# wlpkt1_wejscia.net
KiCad netlist of a schematic drawn in Altium Designer
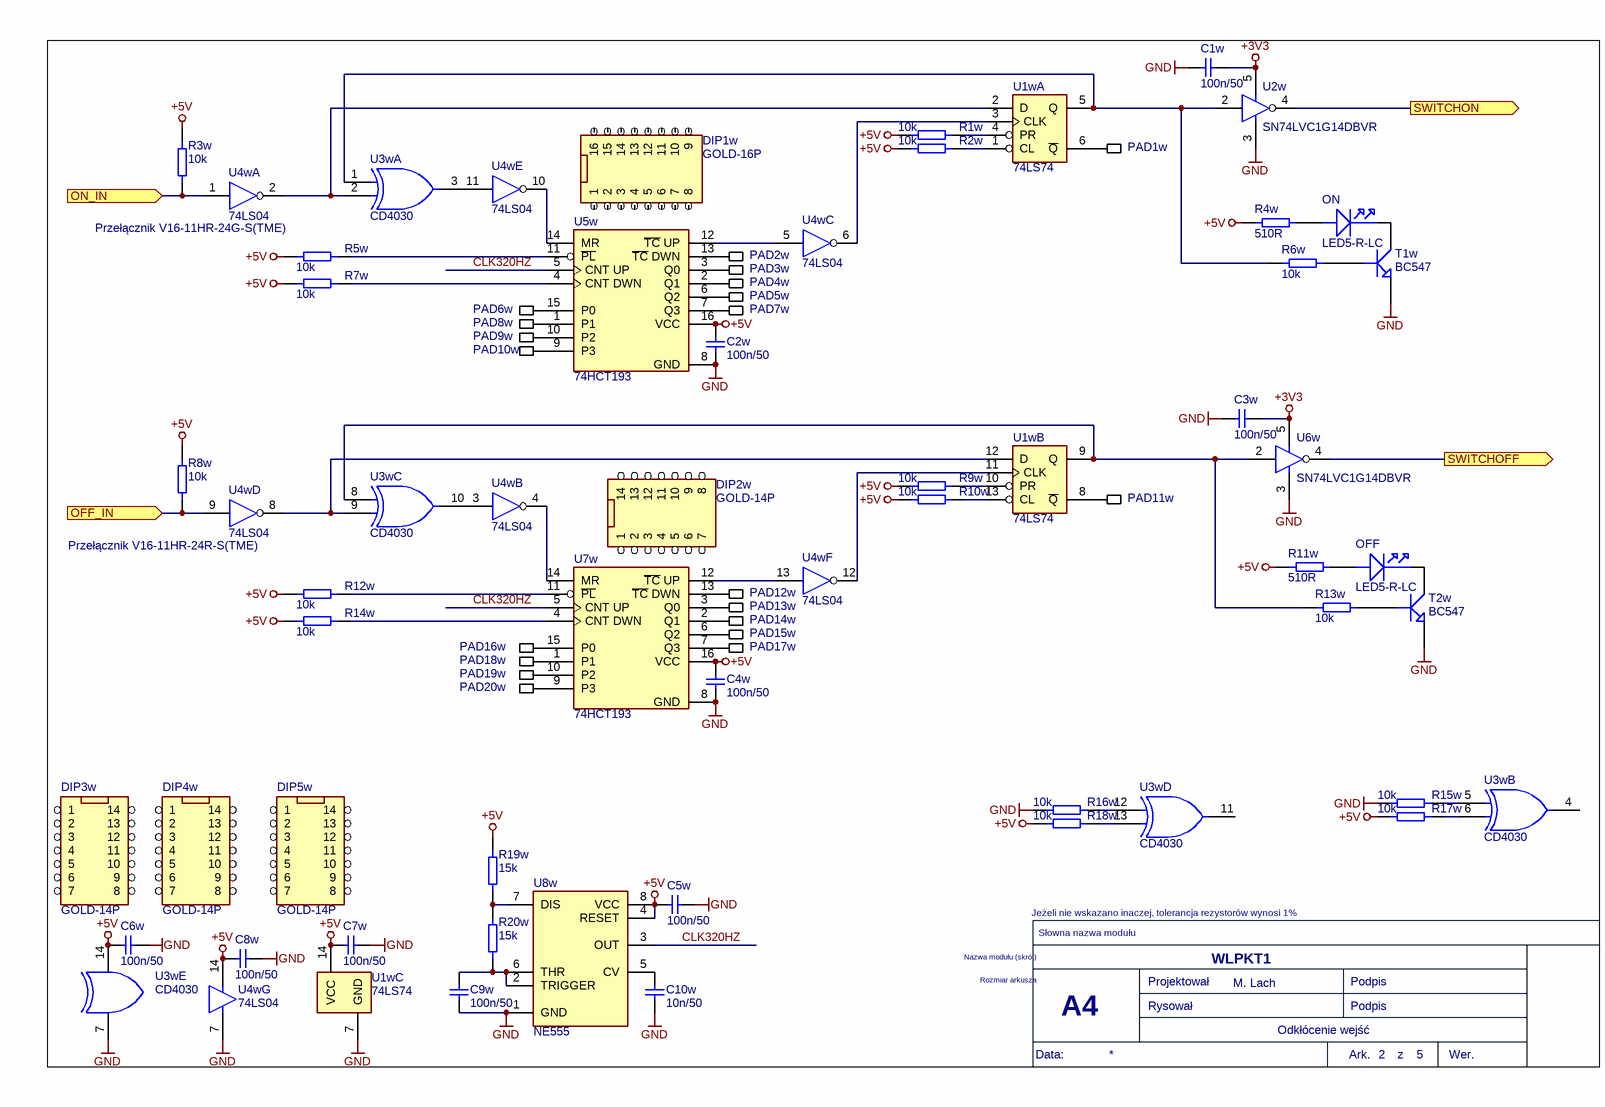
[diagram p0: wlpkt1_wejscia.SchDoc]

(export (version "E")
  (design (tool "Eeschema 10.0.6"))
  (components
    (comp (ref "C1w") (value "100n/50") (footprint "0805") (libsource (lib "PartsMySQL") (part "C")))
    (comp (ref "C2w") (value "100n/50") (footprint "0805") (libsource (lib "PartsMySQL") (part "C")))
    (comp (ref "C3w") (value "100n/50") (footprint "0805") (libsource (lib "PartsMySQL") (part "C")))
    (comp (ref "C4w") (value "100n/50") (footprint "0805") (libsource (lib "PartsMySQL") (part "C")))
    (comp (ref "C5w") (value "100n/50") (footprint "0805") (libsource (lib "PartsMySQL") (part "C")))
    (comp (ref "C6w") (value "100n/50") (footprint "0805") (libsource (lib "PartsMySQL") (part "C")))
    (comp (ref "C7w") (value "100n/50") (footprint "0805") (libsource (lib "PartsMySQL") (part "C")))
    (comp (ref "C8w") (value "100n/50") (footprint "0805") (libsource (lib "PartsMySQL") (part "C")))
    (comp (ref "C9w") (value "100n/50") (footprint "0805") (libsource (lib "PartsMySQL") (part "C")))
    (comp (ref "C10w") (value "10n/50") (footprint "0805") (libsource (lib "PartsMySQL") (part "C")))
    (comp (ref "DIP1w") (value "GOLD-16P") (libsource (lib "PartsMySQL") (part "DIP16MECH")))
    (comp (ref "DIP2w") (value "GOLD-14P") (libsource (lib "") (part "DIP14MECH_1")))
    (comp (ref "DIP3w") (value "GOLD-14P") (libsource (lib "PartsMySQL") (part "DIP14MECH")))
    (comp (ref "DIP4w") (value "GOLD-14P") (libsource (lib "PartsMySQL") (part "DIP14MECH")))
    (comp (ref "DIP5w") (value "GOLD-14P") (libsource (lib "PartsMySQL") (part "DIP14MECH")))
    (comp (ref "OFF") (value "LED5-R-LC") (footprint "CO26") (libsource (lib "PartsMySQL") (part "LED")))
    (comp (ref "ON") (value "LED5-R-LC") (footprint "CO26") (libsource (lib "PartsMySQL") (part "LED")))
    (comp (ref "PAD1w")
      (value "PAD0_6MM")
      (footprint "PAD0_6MM")
      (libsource (lib "PartsMySQL") (part "CLAMP_NOBOM"))
    )
    (comp (ref "PAD2w")
      (value "PAD0_6MM")
      (footprint "PAD0_6MM")
      (libsource (lib "PartsMySQL") (part "CLAMP_NOBOM"))
    )
    (comp (ref "PAD3w")
      (value "PAD0_6MM")
      (footprint "PAD0_6MM")
      (libsource (lib "PartsMySQL") (part "CLAMP_NOBOM"))
    )
    (comp (ref "PAD4w")
      (value "PAD0_6MM")
      (footprint "PAD0_6MM")
      (libsource (lib "PartsMySQL") (part "CLAMP_NOBOM"))
    )
    (comp (ref "PAD5w")
      (value "PAD0_6MM")
      (footprint "PAD0_6MM")
      (libsource (lib "PartsMySQL") (part "CLAMP_NOBOM"))
    )
    (comp (ref "PAD6w") (value "PAD0_6MM") (footprint "PAD0_6MM") (libsource (lib "") (part "CLAMP_NOBOM_1")))
    (comp (ref "PAD7w")
      (value "PAD0_6MM")
      (footprint "PAD0_6MM")
      (libsource (lib "PartsMySQL") (part "CLAMP_NOBOM"))
    )
    (comp (ref "PAD8w") (value "PAD0_6MM") (footprint "PAD0_6MM") (libsource (lib "") (part "CLAMP_NOBOM_1")))
    (comp (ref "PAD9w") (value "PAD0_6MM") (footprint "PAD0_6MM") (libsource (lib "") (part "CLAMP_NOBOM_1")))
    (comp (ref "PAD10w")
      (value "PAD0_6MM")
      (footprint "PAD0_6MM")
      (libsource (lib "") (part "CLAMP_NOBOM_1"))
    )
    (comp (ref "PAD11w")
      (value "PAD0_6MM")
      (footprint "PAD0_6MM")
      (libsource (lib "PartsMySQL") (part "CLAMP_NOBOM"))
    )
    (comp (ref "PAD12w")
      (value "PAD0_6MM")
      (footprint "PAD0_6MM")
      (libsource (lib "PartsMySQL") (part "CLAMP_NOBOM"))
    )
    (comp (ref "PAD13w")
      (value "PAD0_6MM")
      (footprint "PAD0_6MM")
      (libsource (lib "PartsMySQL") (part "CLAMP_NOBOM"))
    )
    (comp (ref "PAD14w")
      (value "PAD0_6MM")
      (footprint "PAD0_6MM")
      (libsource (lib "PartsMySQL") (part "CLAMP_NOBOM"))
    )
    (comp (ref "PAD15w")
      (value "PAD0_6MM")
      (footprint "PAD0_6MM")
      (libsource (lib "PartsMySQL") (part "CLAMP_NOBOM"))
    )
    (comp (ref "PAD16w")
      (value "PAD0_6MM")
      (footprint "PAD0_6MM")
      (libsource (lib "") (part "CLAMP_NOBOM_1"))
    )
    (comp (ref "PAD17w")
      (value "PAD0_6MM")
      (footprint "PAD0_6MM")
      (libsource (lib "PartsMySQL") (part "CLAMP_NOBOM"))
    )
    (comp (ref "PAD18w")
      (value "PAD0_6MM")
      (footprint "PAD0_6MM")
      (libsource (lib "") (part "CLAMP_NOBOM_1"))
    )
    (comp (ref "PAD19w")
      (value "PAD0_6MM")
      (footprint "PAD0_6MM")
      (libsource (lib "") (part "CLAMP_NOBOM_1"))
    )
    (comp (ref "PAD20w")
      (value "PAD0_6MM")
      (footprint "PAD0_6MM")
      (libsource (lib "") (part "CLAMP_NOBOM_1"))
    )
    (comp (ref "R1w") (value "10k") (footprint "0805R") (libsource (lib "PartsMySQL") (part "R")))
    (comp (ref "R2w") (value "10k") (footprint "0805R") (libsource (lib "PartsMySQL") (part "R")))
    (comp (ref "R3w") (value "10k") (footprint "0805R") (libsource (lib "PartsMySQL") (part "R")))
    (comp (ref "R4w") (value "510R") (footprint "R402510") (libsource (lib "PartsMySQL") (part "R")))
    (comp (ref "R5w") (value "10k") (footprint "0805R") (libsource (lib "PartsMySQL") (part "R")))
    (comp (ref "R6w") (value "10k") (footprint "0805R") (libsource (lib "PartsMySQL") (part "R")))
    (comp (ref "R7w") (value "10k") (footprint "0805R") (libsource (lib "PartsMySQL") (part "R")))
    (comp (ref "R8w") (value "10k") (footprint "0805R") (libsource (lib "PartsMySQL") (part "R")))
    (comp (ref "R9w") (value "10k") (footprint "0805R") (libsource (lib "PartsMySQL") (part "R")))
    (comp (ref "R10w") (value "10k") (footprint "0805R") (libsource (lib "PartsMySQL") (part "R")))
    (comp (ref "R11w") (value "510R") (footprint "R402510") (libsource (lib "PartsMySQL") (part "R")))
    (comp (ref "R12w") (value "10k") (footprint "0805R") (libsource (lib "PartsMySQL") (part "R")))
    (comp (ref "R13w") (value "10k") (footprint "0805R") (libsource (lib "PartsMySQL") (part "R")))
    (comp (ref "R14w") (value "10k") (footprint "0805R") (libsource (lib "PartsMySQL") (part "R")))
    (comp (ref "R15w") (value "10k") (footprint "0805R") (libsource (lib "PartsMySQL") (part "R")))
    (comp (ref "R16w") (value "10k") (footprint "0805R") (libsource (lib "PartsMySQL") (part "R")))
    (comp (ref "R17w") (value "10k") (footprint "0805R") (libsource (lib "PartsMySQL") (part "R")))
    (comp (ref "R18w") (value "10k") (footprint "0805R") (libsource (lib "PartsMySQL") (part "R")))
    (comp (ref "R19w") (value "15k") (footprint "0805R") (libsource (lib "PartsMySQL") (part "R")))
    (comp (ref "R20w") (value "15k") (footprint "0805R") (libsource (lib "PartsMySQL") (part "R")))
    (comp (ref "T1w") (value "BC547") (footprint "CE35V4") (libsource (lib "PartsMySQL") (part "NPN_CE35V4")))
    (comp (ref "T2w") (value "BC547") (footprint "CE35V4") (libsource (lib "PartsMySQL") (part "NPN_CE35V4")))
    (comp (ref "U1w") (value "74LS74") (footprint "14DIP300") (libsource (lib "PartsMySQL") (part "7474")))
    (comp (ref "U2w")
      (value "SN74LVC1G14DBVR")
      (footprint "SOT23-5")
      (libsource (lib "PartsMySQL") (part "SN74LVC1G14DB"))
    )
    (comp (ref "U3w") (value "CD4030") (footprint "14DIP300") (libsource (lib "PartsMySQL") (part "CD4030")))
    (comp (ref "U4w") (value "74LS04") (footprint "14DIP300") (libsource (lib "PartsMySQL") (part "7404")))
    (comp (ref "U5w")
      (value "74HCT193")
      (footprint "16DIP300")
      (libsource (lib "PartsMySQL") (part "SN74LS193D"))
    )
    (comp (ref "U6w")
      (value "SN74LVC1G14DBVR")
      (footprint "SOT23-5")
      (libsource (lib "PartsMySQL") (part "SN74LVC1G14DB"))
    )
    (comp (ref "U7w")
      (value "74HCT193")
      (footprint "16DIP300")
      (libsource (lib "PartsMySQL") (part "SN74LS193D"))
    )
    (comp (ref "U8w") (value "NE555") (footprint "8DIP300") (libsource (lib "PartsMySQL") (part "NE555")))
  )
  (nets
    (net (code "1") (name "+3V3") (class "Default")
      (node (ref "C1w") (pin "1") (pinfunction "1_1") (pintype "passive"))
      (node (ref "C3w") (pin "1") (pinfunction "1_1") (pintype "passive"))
      (node (ref "U2w") (pin "5") (pinfunction "VCC_5") (pintype "passive"))
      (node (ref "U6w") (pin "5") (pinfunction "VCC_5") (pintype "passive"))
    )
    (net (code "2") (name "+5V") (class "Default")
      (node (ref "C2w") (pin "1") (pinfunction "1_1") (pintype "passive"))
      (node (ref "C4w") (pin "1") (pinfunction "1_1") (pintype "passive"))
      (node (ref "C5w") (pin "1") (pinfunction "1_1") (pintype "passive"))
      (node (ref "C6w") (pin "1") (pinfunction "1_1") (pintype "passive"))
      (node (ref "C7w") (pin "1") (pinfunction "1_1") (pintype "passive"))
      (node (ref "C8w") (pin "1") (pinfunction "1_1") (pintype "passive"))
      (node (ref "R10w") (pin "1") (pinfunction "1_1") (pintype "passive"))
      (node (ref "R11w") (pin "1") (pinfunction "1_1") (pintype "passive"))
      (node (ref "R12w") (pin "1") (pinfunction "1_1") (pintype "passive"))
      (node (ref "R14w") (pin "1") (pinfunction "1_1") (pintype "passive"))
      (node (ref "R17w") (pin "1") (pinfunction "1_1") (pintype "passive"))
      (node (ref "R18w") (pin "1") (pinfunction "1_1") (pintype "passive"))
      (node (ref "R19w") (pin "1") (pinfunction "1_1") (pintype "passive"))
      (node (ref "R1w") (pin "1") (pinfunction "1_1") (pintype "passive"))
      (node (ref "R2w") (pin "1") (pinfunction "1_1") (pintype "passive"))
      (node (ref "R3w") (pin "1") (pinfunction "1_1") (pintype "passive"))
      (node (ref "R4w") (pin "1") (pinfunction "1_1") (pintype "passive"))
      (node (ref "R5w") (pin "1") (pinfunction "1_1") (pintype "passive"))
      (node (ref "R7w") (pin "1") (pinfunction "1_1") (pintype "passive"))
      (node (ref "R8w") (pin "1") (pinfunction "1_1") (pintype "passive"))
      (node (ref "R9w") (pin "1") (pinfunction "1_1") (pintype "passive"))
      (node (ref "U1w") (pin "14") (pinfunction "VCC_14") (pintype "passive"))
      (node (ref "U3w") (pin "14") (pinfunction "VCC_14") (pintype "passive"))
      (node (ref "U4w") (pin "14") (pinfunction "VCC_14") (pintype "passive"))
      (node (ref "U5w") (pin "16") (pinfunction "VCC_16") (pintype "passive"))
      (node (ref "U7w") (pin "16") (pinfunction "VCC_16") (pintype "passive"))
      (node (ref "U8w") (pin "4") (pinfunction "RESET_4") (pintype "passive"))
      (node (ref "U8w") (pin "8") (pinfunction "VCC_8") (pintype "passive"))
    )
    (net (code "3") (name "/CLK320HZ") (class "Default")
      (node (ref "U5w") (pin "5") (pinfunction "CNT_UP_5") (pintype "passive"))
      (node (ref "U7w") (pin "5") (pinfunction "CNT_UP_5") (pintype "passive"))
      (node (ref "U8w") (pin "3") (pinfunction "OUT_3") (pintype "passive"))
    )
    (net (code "4") (name "/OFF_IN") (class "Default")
      (node (ref "R8w") (pin "2") (pinfunction "2_2") (pintype "passive"))
      (node (ref "U4w") (pin "9") (pinfunction "I_9") (pintype "passive"))
    )
    (net (code "5") (name "/ON_IN") (class "Default")
      (node (ref "R3w") (pin "2") (pinfunction "2_2") (pintype "passive"))
      (node (ref "U4w") (pin "1") (pinfunction "I_1") (pintype "passive"))
    )
    (net (code "6") (name "/SWITCHOFF") (class "Default")
      (node (ref "U6w") (pin "4") (pinfunction "O_4") (pintype "passive"))
    )
    (net (code "7") (name "/SWITCHON") (class "Default")
      (node (ref "U2w") (pin "4") (pinfunction "O_4") (pintype "passive"))
    )
    (net (code "8") (name "GND") (class "Default")
      (node (ref "C10w") (pin "2") (pinfunction "2_2") (pintype "passive"))
      (node (ref "C1w") (pin "2") (pinfunction "2_2") (pintype "passive"))
      (node (ref "C2w") (pin "2") (pinfunction "2_2") (pintype "passive"))
      (node (ref "C3w") (pin "2") (pinfunction "2_2") (pintype "passive"))
      (node (ref "C4w") (pin "2") (pinfunction "2_2") (pintype "passive"))
      (node (ref "C5w") (pin "2") (pinfunction "2_2") (pintype "passive"))
      (node (ref "C6w") (pin "2") (pinfunction "2_2") (pintype "passive"))
      (node (ref "C7w") (pin "2") (pinfunction "2_2") (pintype "passive"))
      (node (ref "C8w") (pin "2") (pinfunction "2_2") (pintype "passive"))
      (node (ref "C9w") (pin "2") (pinfunction "2_2") (pintype "passive"))
      (node (ref "R15w") (pin "1") (pinfunction "1_1") (pintype "passive"))
      (node (ref "R16w") (pin "1") (pinfunction "1_1") (pintype "passive"))
      (node (ref "T1w") (pin "EMIT") (pinfunction "EMIT_EMIT") (pintype "passive"))
      (node (ref "T2w") (pin "EMIT") (pinfunction "EMIT_EMIT") (pintype "passive"))
      (node (ref "U1w") (pin "7") (pinfunction "GND_7") (pintype "passive"))
      (node (ref "U2w") (pin "3") (pinfunction "GND_3") (pintype "passive"))
      (node (ref "U3w") (pin "7") (pinfunction "GND_7") (pintype "passive"))
      (node (ref "U4w") (pin "7") (pinfunction "GND_7") (pintype "passive"))
      (node (ref "U5w") (pin "8") (pinfunction "GND_8") (pintype "passive"))
      (node (ref "U6w") (pin "3") (pinfunction "GND_3") (pintype "passive"))
      (node (ref "U7w") (pin "8") (pinfunction "GND_8") (pintype "passive"))
      (node (ref "U8w") (pin "1") (pinfunction "GND_1") (pintype "passive"))
    )
    (net (code "9") (name "Net-(OFF-PadANOD)") (class "Default")
      (node (ref "OFF") (pin "ANOD") (pinfunction "ANOD_ANOD") (pintype "passive"))
      (node (ref "R11w") (pin "2") (pinfunction "2_2") (pintype "passive"))
    )
    (net (code "10") (name "Net-(OFF-PadCATH)") (class "Default")
      (node (ref "OFF") (pin "CATH") (pinfunction "CATH_CATH") (pintype "passive"))
      (node (ref "T2w") (pin "COLL") (pinfunction "COLL_COLL") (pintype "passive"))
    )
    (net (code "11") (name "Net-(ON-PadANOD)") (class "Default")
      (node (ref "ON") (pin "ANOD") (pinfunction "ANOD_ANOD") (pintype "passive"))
      (node (ref "R4w") (pin "2") (pinfunction "2_2") (pintype "passive"))
    )
    (net (code "12") (name "Net-(ON-PadCATH)") (class "Default")
      (node (ref "ON") (pin "CATH") (pinfunction "CATH_CATH") (pintype "passive"))
      (node (ref "T1w") (pin "COLL") (pinfunction "COLL_COLL") (pintype "passive"))
    )
    (net (code "13") (name "Net-(R6w-Pad1)") (class "Default")
      (node (ref "R6w") (pin "1") (pinfunction "1_1") (pintype "passive"))
      (node (ref "T1w") (pin "BASE") (pinfunction "BASE_BASE") (pintype "passive"))
    )
    (net (code "14") (name "Net-(R13w-Pad1)") (class "Default")
      (node (ref "R13w") (pin "1") (pinfunction "1_1") (pintype "passive"))
      (node (ref "T2w") (pin "BASE") (pinfunction "BASE_BASE") (pintype "passive"))
    )
    (net (code "15") (name "Net-(U1wA-CL)") (class "Default")
      (node (ref "R2w") (pin "2") (pinfunction "2_2") (pintype "passive"))
      (node (ref "U1w") (pin "1") (pinfunction "CL_1") (pintype "passive"))
    )
    (net (code "16") (name "Net-(U1wA-CLK)") (class "Default")
      (node (ref "U1w") (pin "3") (pinfunction "CLK_3") (pintype "passive"))
      (node (ref "U4w") (pin "6") (pinfunction "O_6") (pintype "passive"))
    )
    (net (code "17") (name "Net-(U1wA-D)") (class "Default")
      (node (ref "U1w") (pin "2") (pinfunction "D_2") (pintype "passive"))
      (node (ref "U3w") (pin "2") (pinfunction "I1_2") (pintype "passive"))
      (node (ref "U4w") (pin "2") (pinfunction "O_2") (pintype "passive"))
    )
    (net (code "18") (name "Net-(U1wA-PR)") (class "Default")
      (node (ref "R1w") (pin "2") (pinfunction "2_2") (pintype "passive"))
      (node (ref "U1w") (pin "4") (pinfunction "PR_4") (pintype "passive"))
    )
    (net (code "19") (name "Net-(U1wA-Q)") (class "Default")
      (node (ref "R6w") (pin "2") (pinfunction "2_2") (pintype "passive"))
      (node (ref "U1w") (pin "5") (pinfunction "Q_5") (pintype "passive"))
      (node (ref "U2w") (pin "2") (pinfunction "I_2") (pintype "passive"))
      (node (ref "U3w") (pin "1") (pinfunction "I0_1") (pintype "passive"))
    )
    (net (code "20") (name "Net-(U1wA-~{Q})") (class "Default")
      (node (ref "PAD1w") (pin "1") (pinfunction "1_1") (pintype "passive"))
      (node (ref "U1w") (pin "6") (pinfunction "~{Q}_6") (pintype "passive"))
    )
    (net (code "21") (name "Net-(U1wB-CL)") (class "Default")
      (node (ref "R10w") (pin "2") (pinfunction "2_2") (pintype "passive"))
      (node (ref "U1w") (pin "13") (pinfunction "CL_13") (pintype "passive"))
    )
    (net (code "22") (name "Net-(U1wB-CLK)") (class "Default")
      (node (ref "U1w") (pin "11") (pinfunction "CLK_11") (pintype "passive"))
      (node (ref "U4w") (pin "12") (pinfunction "O_12") (pintype "passive"))
    )
    (net (code "23") (name "Net-(U1wB-D)") (class "Default")
      (node (ref "U1w") (pin "12") (pinfunction "D_12") (pintype "passive"))
      (node (ref "U3w") (pin "9") (pinfunction "I1_9") (pintype "passive"))
      (node (ref "U4w") (pin "8") (pinfunction "O_8") (pintype "passive"))
    )
    (net (code "24") (name "Net-(U1wB-PR)") (class "Default")
      (node (ref "R9w") (pin "2") (pinfunction "2_2") (pintype "passive"))
      (node (ref "U1w") (pin "10") (pinfunction "PR_10") (pintype "passive"))
    )
    (net (code "25") (name "Net-(U1wB-Q)") (class "Default")
      (node (ref "R13w") (pin "2") (pinfunction "2_2") (pintype "passive"))
      (node (ref "U1w") (pin "9") (pinfunction "Q_9") (pintype "passive"))
      (node (ref "U3w") (pin "8") (pinfunction "I0_8") (pintype "passive"))
      (node (ref "U6w") (pin "2") (pinfunction "I_2") (pintype "passive"))
    )
    (net (code "26") (name "Net-(U1wB-~{Q})") (class "Default")
      (node (ref "PAD11w") (pin "1") (pinfunction "1_1") (pintype "passive"))
      (node (ref "U1w") (pin "8") (pinfunction "~{Q}_8") (pintype "passive"))
    )
    (net (code "27") (name "Net-(U3wA-O)") (class "Default")
      (node (ref "U3w") (pin "3") (pinfunction "O_3") (pintype "passive"))
      (node (ref "U4w") (pin "11") (pinfunction "I_11") (pintype "passive"))
    )
    (net (code "28") (name "Net-(U3wB-I0)") (class "Default")
      (node (ref "R15w") (pin "2") (pinfunction "2_2") (pintype "passive"))
      (node (ref "U3w") (pin "5") (pinfunction "I0_5") (pintype "passive"))
    )
    (net (code "29") (name "Net-(U3wB-I1)") (class "Default")
      (node (ref "R17w") (pin "2") (pinfunction "2_2") (pintype "passive"))
      (node (ref "U3w") (pin "6") (pinfunction "I1_6") (pintype "passive"))
    )
    (net (code "30") (name "Net-(U3wC-O)") (class "Default")
      (node (ref "U3w") (pin "10") (pinfunction "O_10") (pintype "passive"))
      (node (ref "U4w") (pin "3") (pinfunction "I_3") (pintype "passive"))
    )
    (net (code "31") (name "Net-(U3wD-I0)") (class "Default")
      (node (ref "R16w") (pin "2") (pinfunction "2_2") (pintype "passive"))
      (node (ref "U3w") (pin "12") (pinfunction "I0_12") (pintype "passive"))
    )
    (net (code "32") (name "Net-(U3wD-I1)") (class "Default")
      (node (ref "R18w") (pin "2") (pinfunction "2_2") (pintype "passive"))
      (node (ref "U3w") (pin "13") (pinfunction "I1_13") (pintype "passive"))
    )
    (net (code "33") (name "Net-(U4wB-O)") (class "Default")
      (node (ref "U4w") (pin "4") (pinfunction "O_4") (pintype "passive"))
      (node (ref "U7w") (pin "14") (pinfunction "MR_14") (pintype "passive"))
    )
    (net (code "34") (name "Net-(U4wC-I)") (class "Default")
      (node (ref "U4w") (pin "5") (pinfunction "I_5") (pintype "passive"))
      (node (ref "U5w") (pin "12") (pinfunction "~{TC}_UP_12") (pintype "passive"))
    )
    (net (code "35") (name "Net-(U4wE-O)") (class "Default")
      (node (ref "U4w") (pin "10") (pinfunction "O_10") (pintype "passive"))
      (node (ref "U5w") (pin "14") (pinfunction "MR_14") (pintype "passive"))
    )
    (net (code "36") (name "Net-(U4wF-I)") (class "Default")
      (node (ref "U4w") (pin "13") (pinfunction "I_13") (pintype "passive"))
      (node (ref "U7w") (pin "12") (pinfunction "~{TC}_UP_12") (pintype "passive"))
    )
    (net (code "37") (name "Net-(U5w-CNT_DWN)") (class "Default")
      (node (ref "R7w") (pin "2") (pinfunction "2_2") (pintype "passive"))
      (node (ref "U5w") (pin "4") (pinfunction "CNT_DWN_4") (pintype "passive"))
    )
    (net (code "38") (name "Net-(U5w-P0)") (class "Default")
      (node (ref "PAD6w") (pin "1") (pinfunction "1_1") (pintype "passive"))
      (node (ref "U5w") (pin "15") (pinfunction "P0_15") (pintype "passive"))
    )
    (net (code "39") (name "Net-(U5w-P1)") (class "Default")
      (node (ref "PAD8w") (pin "1") (pinfunction "1_1") (pintype "passive"))
      (node (ref "U5w") (pin "1") (pinfunction "P1_1") (pintype "passive"))
    )
    (net (code "40") (name "Net-(U5w-P2)") (class "Default")
      (node (ref "PAD9w") (pin "1") (pinfunction "1_1") (pintype "passive"))
      (node (ref "U5w") (pin "10") (pinfunction "P2_10") (pintype "passive"))
    )
    (net (code "41") (name "Net-(U5w-P3)") (class "Default")
      (node (ref "PAD10w") (pin "1") (pinfunction "1_1") (pintype "passive"))
      (node (ref "U5w") (pin "9") (pinfunction "P3_9") (pintype "passive"))
    )
    (net (code "42") (name "Net-(U5w-Q0)") (class "Default")
      (node (ref "PAD3w") (pin "1") (pinfunction "1_1") (pintype "passive"))
      (node (ref "U5w") (pin "3") (pinfunction "Q0_3") (pintype "passive"))
    )
    (net (code "43") (name "Net-(U5w-Q1)") (class "Default")
      (node (ref "PAD4w") (pin "1") (pinfunction "1_1") (pintype "passive"))
      (node (ref "U5w") (pin "2") (pinfunction "Q1_2") (pintype "passive"))
    )
    (net (code "44") (name "Net-(U5w-Q2)") (class "Default")
      (node (ref "PAD5w") (pin "1") (pinfunction "1_1") (pintype "passive"))
      (node (ref "U5w") (pin "6") (pinfunction "Q2_6") (pintype "passive"))
    )
    (net (code "45") (name "Net-(U5w-Q3)") (class "Default")
      (node (ref "PAD7w") (pin "1") (pinfunction "1_1") (pintype "passive"))
      (node (ref "U5w") (pin "7") (pinfunction "Q3_7") (pintype "passive"))
    )
    (net (code "46") (name "Net-(U5w-~{PL})") (class "Default")
      (node (ref "R5w") (pin "2") (pinfunction "2_2") (pintype "passive"))
      (node (ref "U5w") (pin "11") (pinfunction "~{PL}_11") (pintype "passive"))
    )
    (net (code "47") (name "Net-(U5w-~{TC}_DWN)") (class "Default")
      (node (ref "PAD2w") (pin "1") (pinfunction "1_1") (pintype "passive"))
      (node (ref "U5w") (pin "13") (pinfunction "~{TC}_DWN_13") (pintype "passive"))
    )
    (net (code "48") (name "Net-(U7w-CNT_DWN)") (class "Default")
      (node (ref "R14w") (pin "2") (pinfunction "2_2") (pintype "passive"))
      (node (ref "U7w") (pin "4") (pinfunction "CNT_DWN_4") (pintype "passive"))
    )
    (net (code "49") (name "Net-(U7w-P0)") (class "Default")
      (node (ref "PAD16w") (pin "1") (pinfunction "1_1") (pintype "passive"))
      (node (ref "U7w") (pin "15") (pinfunction "P0_15") (pintype "passive"))
    )
    (net (code "50") (name "Net-(U7w-P1)") (class "Default")
      (node (ref "PAD18w") (pin "1") (pinfunction "1_1") (pintype "passive"))
      (node (ref "U7w") (pin "1") (pinfunction "P1_1") (pintype "passive"))
    )
    (net (code "51") (name "Net-(U7w-P2)") (class "Default")
      (node (ref "PAD19w") (pin "1") (pinfunction "1_1") (pintype "passive"))
      (node (ref "U7w") (pin "10") (pinfunction "P2_10") (pintype "passive"))
    )
    (net (code "52") (name "Net-(U7w-P3)") (class "Default")
      (node (ref "PAD20w") (pin "1") (pinfunction "1_1") (pintype "passive"))
      (node (ref "U7w") (pin "9") (pinfunction "P3_9") (pintype "passive"))
    )
    (net (code "53") (name "Net-(U7w-Q0)") (class "Default")
      (node (ref "PAD13w") (pin "1") (pinfunction "1_1") (pintype "passive"))
      (node (ref "U7w") (pin "3") (pinfunction "Q0_3") (pintype "passive"))
    )
    (net (code "54") (name "Net-(U7w-Q1)") (class "Default")
      (node (ref "PAD14w") (pin "1") (pinfunction "1_1") (pintype "passive"))
      (node (ref "U7w") (pin "2") (pinfunction "Q1_2") (pintype "passive"))
    )
    (net (code "55") (name "Net-(U7w-Q2)") (class "Default")
      (node (ref "PAD15w") (pin "1") (pinfunction "1_1") (pintype "passive"))
      (node (ref "U7w") (pin "6") (pinfunction "Q2_6") (pintype "passive"))
    )
    (net (code "56") (name "Net-(U7w-Q3)") (class "Default")
      (node (ref "PAD17w") (pin "1") (pinfunction "1_1") (pintype "passive"))
      (node (ref "U7w") (pin "7") (pinfunction "Q3_7") (pintype "passive"))
    )
    (net (code "57") (name "Net-(U7w-~{PL})") (class "Default")
      (node (ref "R12w") (pin "2") (pinfunction "2_2") (pintype "passive"))
      (node (ref "U7w") (pin "11") (pinfunction "~{PL}_11") (pintype "passive"))
    )
    (net (code "58") (name "Net-(U7w-~{TC}_DWN)") (class "Default")
      (node (ref "PAD12w") (pin "1") (pinfunction "1_1") (pintype "passive"))
      (node (ref "U7w") (pin "13") (pinfunction "~{TC}_DWN_13") (pintype "passive"))
    )
    (net (code "59") (name "Net-(U8w-CV)") (class "Default")
      (node (ref "C10w") (pin "1") (pinfunction "1_1") (pintype "passive"))
      (node (ref "U8w") (pin "5") (pinfunction "CV_5") (pintype "passive"))
    )
    (net (code "60") (name "Net-(U8w-DIS)") (class "Default")
      (node (ref "R19w") (pin "2") (pinfunction "2_2") (pintype "passive"))
      (node (ref "R20w") (pin "1") (pinfunction "1_1") (pintype "passive"))
      (node (ref "U8w") (pin "7") (pinfunction "DIS_7") (pintype "passive"))
    )
    (net (code "61") (name "Net-(U8w-THR)") (class "Default")
      (node (ref "C9w") (pin "1") (pinfunction "1_1") (pintype "passive"))
      (node (ref "R20w") (pin "2") (pinfunction "2_2") (pintype "passive"))
      (node (ref "U8w") (pin "2") (pinfunction "TRIGGER_2") (pintype "passive"))
      (node (ref "U8w") (pin "6") (pinfunction "THR_6") (pintype "passive"))
    )
    (net (code "62") (name "unconnected-(DIP1w-Pad1)") (class "Default")
      (node (ref "DIP1w") (pin "1") (pinfunction "1_1") (pintype "passive"))
    )
    (net (code "63") (name "unconnected-(DIP1w-Pad2)") (class "Default")
      (node (ref "DIP1w") (pin "2") (pinfunction "2_2") (pintype "passive"))
    )
    (net (code "64") (name "unconnected-(DIP1w-Pad3)") (class "Default")
      (node (ref "DIP1w") (pin "3") (pinfunction "3_3") (pintype "passive"))
    )
    (net (code "65") (name "unconnected-(DIP1w-Pad4)") (class "Default")
      (node (ref "DIP1w") (pin "4") (pinfunction "4_4") (pintype "passive"))
    )
    (net (code "66") (name "unconnected-(DIP1w-Pad5)") (class "Default")
      (node (ref "DIP1w") (pin "5") (pinfunction "5_5") (pintype "passive"))
    )
    (net (code "67") (name "unconnected-(DIP1w-Pad6)") (class "Default")
      (node (ref "DIP1w") (pin "6") (pinfunction "6_6") (pintype "passive"))
    )
    (net (code "68") (name "unconnected-(DIP1w-Pad7)") (class "Default")
      (node (ref "DIP1w") (pin "7") (pinfunction "7_7") (pintype "passive"))
    )
    (net (code "69") (name "unconnected-(DIP1w-Pad8)") (class "Default")
      (node (ref "DIP1w") (pin "8") (pinfunction "8_8") (pintype "passive"))
    )
    (net (code "70") (name "unconnected-(DIP1w-Pad9)") (class "Default")
      (node (ref "DIP1w") (pin "9") (pinfunction "9_9") (pintype "passive"))
    )
    (net (code "71") (name "unconnected-(DIP1w-Pad10)") (class "Default")
      (node (ref "DIP1w") (pin "10") (pinfunction "10_10") (pintype "passive"))
    )
    (net (code "72") (name "unconnected-(DIP1w-Pad11)") (class "Default")
      (node (ref "DIP1w") (pin "11") (pinfunction "11_11") (pintype "passive"))
    )
    (net (code "73") (name "unconnected-(DIP1w-Pad12)") (class "Default")
      (node (ref "DIP1w") (pin "12") (pinfunction "12_12") (pintype "passive"))
    )
    (net (code "74") (name "unconnected-(DIP1w-Pad13)") (class "Default")
      (node (ref "DIP1w") (pin "13") (pinfunction "13_13") (pintype "passive"))
    )
    (net (code "75") (name "unconnected-(DIP1w-Pad14)") (class "Default")
      (node (ref "DIP1w") (pin "14") (pinfunction "14_14") (pintype "passive"))
    )
    (net (code "76") (name "unconnected-(DIP1w-Pad15)") (class "Default")
      (node (ref "DIP1w") (pin "15") (pinfunction "15_15") (pintype "passive"))
    )
    (net (code "77") (name "unconnected-(DIP1w-Pad16)") (class "Default")
      (node (ref "DIP1w") (pin "16") (pinfunction "16_16") (pintype "passive"))
    )
    (net (code "78") (name "unconnected-(DIP2w-Pad1)") (class "Default")
      (node (ref "DIP2w") (pin "1") (pinfunction "1_1") (pintype "passive"))
    )
    (net (code "79") (name "unconnected-(DIP2w-Pad2)") (class "Default")
      (node (ref "DIP2w") (pin "2") (pinfunction "2_2") (pintype "passive"))
    )
    (net (code "80") (name "unconnected-(DIP2w-Pad3)") (class "Default")
      (node (ref "DIP2w") (pin "3") (pinfunction "3_3") (pintype "passive"))
    )
    (net (code "81") (name "unconnected-(DIP2w-Pad4)") (class "Default")
      (node (ref "DIP2w") (pin "4") (pinfunction "4_4") (pintype "passive"))
    )
    (net (code "82") (name "unconnected-(DIP2w-Pad5)") (class "Default")
      (node (ref "DIP2w") (pin "5") (pinfunction "5_5") (pintype "passive"))
    )
    (net (code "83") (name "unconnected-(DIP2w-Pad6)") (class "Default")
      (node (ref "DIP2w") (pin "6") (pinfunction "6_6") (pintype "passive"))
    )
    (net (code "84") (name "unconnected-(DIP2w-Pad7)") (class "Default")
      (node (ref "DIP2w") (pin "7") (pinfunction "7_7") (pintype "passive"))
    )
    (net (code "85") (name "unconnected-(DIP2w-Pad8)") (class "Default")
      (node (ref "DIP2w") (pin "8") (pinfunction "8_8") (pintype "passive"))
    )
    (net (code "86") (name "unconnected-(DIP2w-Pad9)") (class "Default")
      (node (ref "DIP2w") (pin "9") (pinfunction "9_9") (pintype "passive"))
    )
    (net (code "87") (name "unconnected-(DIP2w-Pad10)") (class "Default")
      (node (ref "DIP2w") (pin "10") (pinfunction "10_10") (pintype "passive"))
    )
    (net (code "88") (name "unconnected-(DIP2w-Pad11)") (class "Default")
      (node (ref "DIP2w") (pin "11") (pinfunction "11_11") (pintype "passive"))
    )
    (net (code "89") (name "unconnected-(DIP2w-Pad12)") (class "Default")
      (node (ref "DIP2w") (pin "12") (pinfunction "12_12") (pintype "passive"))
    )
    (net (code "90") (name "unconnected-(DIP2w-Pad13)") (class "Default")
      (node (ref "DIP2w") (pin "13") (pinfunction "13_13") (pintype "passive"))
    )
    (net (code "91") (name "unconnected-(DIP2w-Pad14)") (class "Default")
      (node (ref "DIP2w") (pin "14") (pinfunction "14_14") (pintype "passive"))
    )
    (net (code "92") (name "unconnected-(DIP3w-Pad1)") (class "Default")
      (node (ref "DIP3w") (pin "1") (pinfunction "1_1") (pintype "passive"))
    )
    (net (code "93") (name "unconnected-(DIP3w-Pad2)") (class "Default")
      (node (ref "DIP3w") (pin "2") (pinfunction "2_2") (pintype "passive"))
    )
    (net (code "94") (name "unconnected-(DIP3w-Pad3)") (class "Default")
      (node (ref "DIP3w") (pin "3") (pinfunction "3_3") (pintype "passive"))
    )
    (net (code "95") (name "unconnected-(DIP3w-Pad4)") (class "Default")
      (node (ref "DIP3w") (pin "4") (pinfunction "4_4") (pintype "passive"))
    )
    (net (code "96") (name "unconnected-(DIP3w-Pad5)") (class "Default")
      (node (ref "DIP3w") (pin "5") (pinfunction "5_5") (pintype "passive"))
    )
    (net (code "97") (name "unconnected-(DIP3w-Pad6)") (class "Default")
      (node (ref "DIP3w") (pin "6") (pinfunction "6_6") (pintype "passive"))
    )
    (net (code "98") (name "unconnected-(DIP3w-Pad7)") (class "Default")
      (node (ref "DIP3w") (pin "7") (pinfunction "7_7") (pintype "passive"))
    )
    (net (code "99") (name "unconnected-(DIP3w-Pad8)") (class "Default")
      (node (ref "DIP3w") (pin "8") (pinfunction "8_8") (pintype "passive"))
    )
    (net (code "100") (name "unconnected-(DIP3w-Pad9)") (class "Default")
      (node (ref "DIP3w") (pin "9") (pinfunction "9_9") (pintype "passive"))
    )
    (net (code "101") (name "unconnected-(DIP3w-Pad10)") (class "Default")
      (node (ref "DIP3w") (pin "10") (pinfunction "10_10") (pintype "passive"))
    )
    (net (code "102") (name "unconnected-(DIP3w-Pad11)") (class "Default")
      (node (ref "DIP3w") (pin "11") (pinfunction "11_11") (pintype "passive"))
    )
    (net (code "103") (name "unconnected-(DIP3w-Pad12)") (class "Default")
      (node (ref "DIP3w") (pin "12") (pinfunction "12_12") (pintype "passive"))
    )
    (net (code "104") (name "unconnected-(DIP3w-Pad13)") (class "Default")
      (node (ref "DIP3w") (pin "13") (pinfunction "13_13") (pintype "passive"))
    )
    (net (code "105") (name "unconnected-(DIP3w-Pad14)") (class "Default")
      (node (ref "DIP3w") (pin "14") (pinfunction "14_14") (pintype "passive"))
    )
    (net (code "106") (name "unconnected-(DIP4w-Pad1)") (class "Default")
      (node (ref "DIP4w") (pin "1") (pinfunction "1_1") (pintype "passive"))
    )
    (net (code "107") (name "unconnected-(DIP4w-Pad2)") (class "Default")
      (node (ref "DIP4w") (pin "2") (pinfunction "2_2") (pintype "passive"))
    )
    (net (code "108") (name "unconnected-(DIP4w-Pad3)") (class "Default")
      (node (ref "DIP4w") (pin "3") (pinfunction "3_3") (pintype "passive"))
    )
    (net (code "109") (name "unconnected-(DIP4w-Pad4)") (class "Default")
      (node (ref "DIP4w") (pin "4") (pinfunction "4_4") (pintype "passive"))
    )
    (net (code "110") (name "unconnected-(DIP4w-Pad5)") (class "Default")
      (node (ref "DIP4w") (pin "5") (pinfunction "5_5") (pintype "passive"))
    )
    (net (code "111") (name "unconnected-(DIP4w-Pad6)") (class "Default")
      (node (ref "DIP4w") (pin "6") (pinfunction "6_6") (pintype "passive"))
    )
    (net (code "112") (name "unconnected-(DIP4w-Pad7)") (class "Default")
      (node (ref "DIP4w") (pin "7") (pinfunction "7_7") (pintype "passive"))
    )
    (net (code "113") (name "unconnected-(DIP4w-Pad8)") (class "Default")
      (node (ref "DIP4w") (pin "8") (pinfunction "8_8") (pintype "passive"))
    )
    (net (code "114") (name "unconnected-(DIP4w-Pad9)") (class "Default")
      (node (ref "DIP4w") (pin "9") (pinfunction "9_9") (pintype "passive"))
    )
    (net (code "115") (name "unconnected-(DIP4w-Pad10)") (class "Default")
      (node (ref "DIP4w") (pin "10") (pinfunction "10_10") (pintype "passive"))
    )
    (net (code "116") (name "unconnected-(DIP4w-Pad11)") (class "Default")
      (node (ref "DIP4w") (pin "11") (pinfunction "11_11") (pintype "passive"))
    )
    (net (code "117") (name "unconnected-(DIP4w-Pad12)") (class "Default")
      (node (ref "DIP4w") (pin "12") (pinfunction "12_12") (pintype "passive"))
    )
    (net (code "118") (name "unconnected-(DIP4w-Pad13)") (class "Default")
      (node (ref "DIP4w") (pin "13") (pinfunction "13_13") (pintype "passive"))
    )
    (net (code "119") (name "unconnected-(DIP4w-Pad14)") (class "Default")
      (node (ref "DIP4w") (pin "14") (pinfunction "14_14") (pintype "passive"))
    )
    (net (code "120") (name "unconnected-(DIP5w-Pad1)") (class "Default")
      (node (ref "DIP5w") (pin "1") (pinfunction "1_1") (pintype "passive"))
    )
    (net (code "121") (name "unconnected-(DIP5w-Pad2)") (class "Default")
      (node (ref "DIP5w") (pin "2") (pinfunction "2_2") (pintype "passive"))
    )
    (net (code "122") (name "unconnected-(DIP5w-Pad3)") (class "Default")
      (node (ref "DIP5w") (pin "3") (pinfunction "3_3") (pintype "passive"))
    )
    (net (code "123") (name "unconnected-(DIP5w-Pad4)") (class "Default")
      (node (ref "DIP5w") (pin "4") (pinfunction "4_4") (pintype "passive"))
    )
    (net (code "124") (name "unconnected-(DIP5w-Pad5)") (class "Default")
      (node (ref "DIP5w") (pin "5") (pinfunction "5_5") (pintype "passive"))
    )
    (net (code "125") (name "unconnected-(DIP5w-Pad6)") (class "Default")
      (node (ref "DIP5w") (pin "6") (pinfunction "6_6") (pintype "passive"))
    )
    (net (code "126") (name "unconnected-(DIP5w-Pad7)") (class "Default")
      (node (ref "DIP5w") (pin "7") (pinfunction "7_7") (pintype "passive"))
    )
    (net (code "127") (name "unconnected-(DIP5w-Pad8)") (class "Default")
      (node (ref "DIP5w") (pin "8") (pinfunction "8_8") (pintype "passive"))
    )
    (net (code "128") (name "unconnected-(DIP5w-Pad9)") (class "Default")
      (node (ref "DIP5w") (pin "9") (pinfunction "9_9") (pintype "passive"))
    )
    (net (code "129") (name "unconnected-(DIP5w-Pad10)") (class "Default")
      (node (ref "DIP5w") (pin "10") (pinfunction "10_10") (pintype "passive"))
    )
    (net (code "130") (name "unconnected-(DIP5w-Pad11)") (class "Default")
      (node (ref "DIP5w") (pin "11") (pinfunction "11_11") (pintype "passive"))
    )
    (net (code "131") (name "unconnected-(DIP5w-Pad12)") (class "Default")
      (node (ref "DIP5w") (pin "12") (pinfunction "12_12") (pintype "passive"))
    )
    (net (code "132") (name "unconnected-(DIP5w-Pad13)") (class "Default")
      (node (ref "DIP5w") (pin "13") (pinfunction "13_13") (pintype "passive"))
    )
    (net (code "133") (name "unconnected-(DIP5w-Pad14)") (class "Default")
      (node (ref "DIP5w") (pin "14") (pinfunction "14_14") (pintype "passive"))
    )
    (net (code "134") (name "unconnected-(U3wB-O-Pad4)") (class "Default")
      (node (ref "U3w") (pin "4") (pinfunction "O_4") (pintype "passive"))
    )
    (net (code "135") (name "unconnected-(U3wD-O-Pad11)") (class "Default")
      (node (ref "U3w") (pin "11") (pinfunction "O_11") (pintype "passive"))
    )
  )
)
